# sb6.net
KiCad netlist of a schematic drawn in EAGLE
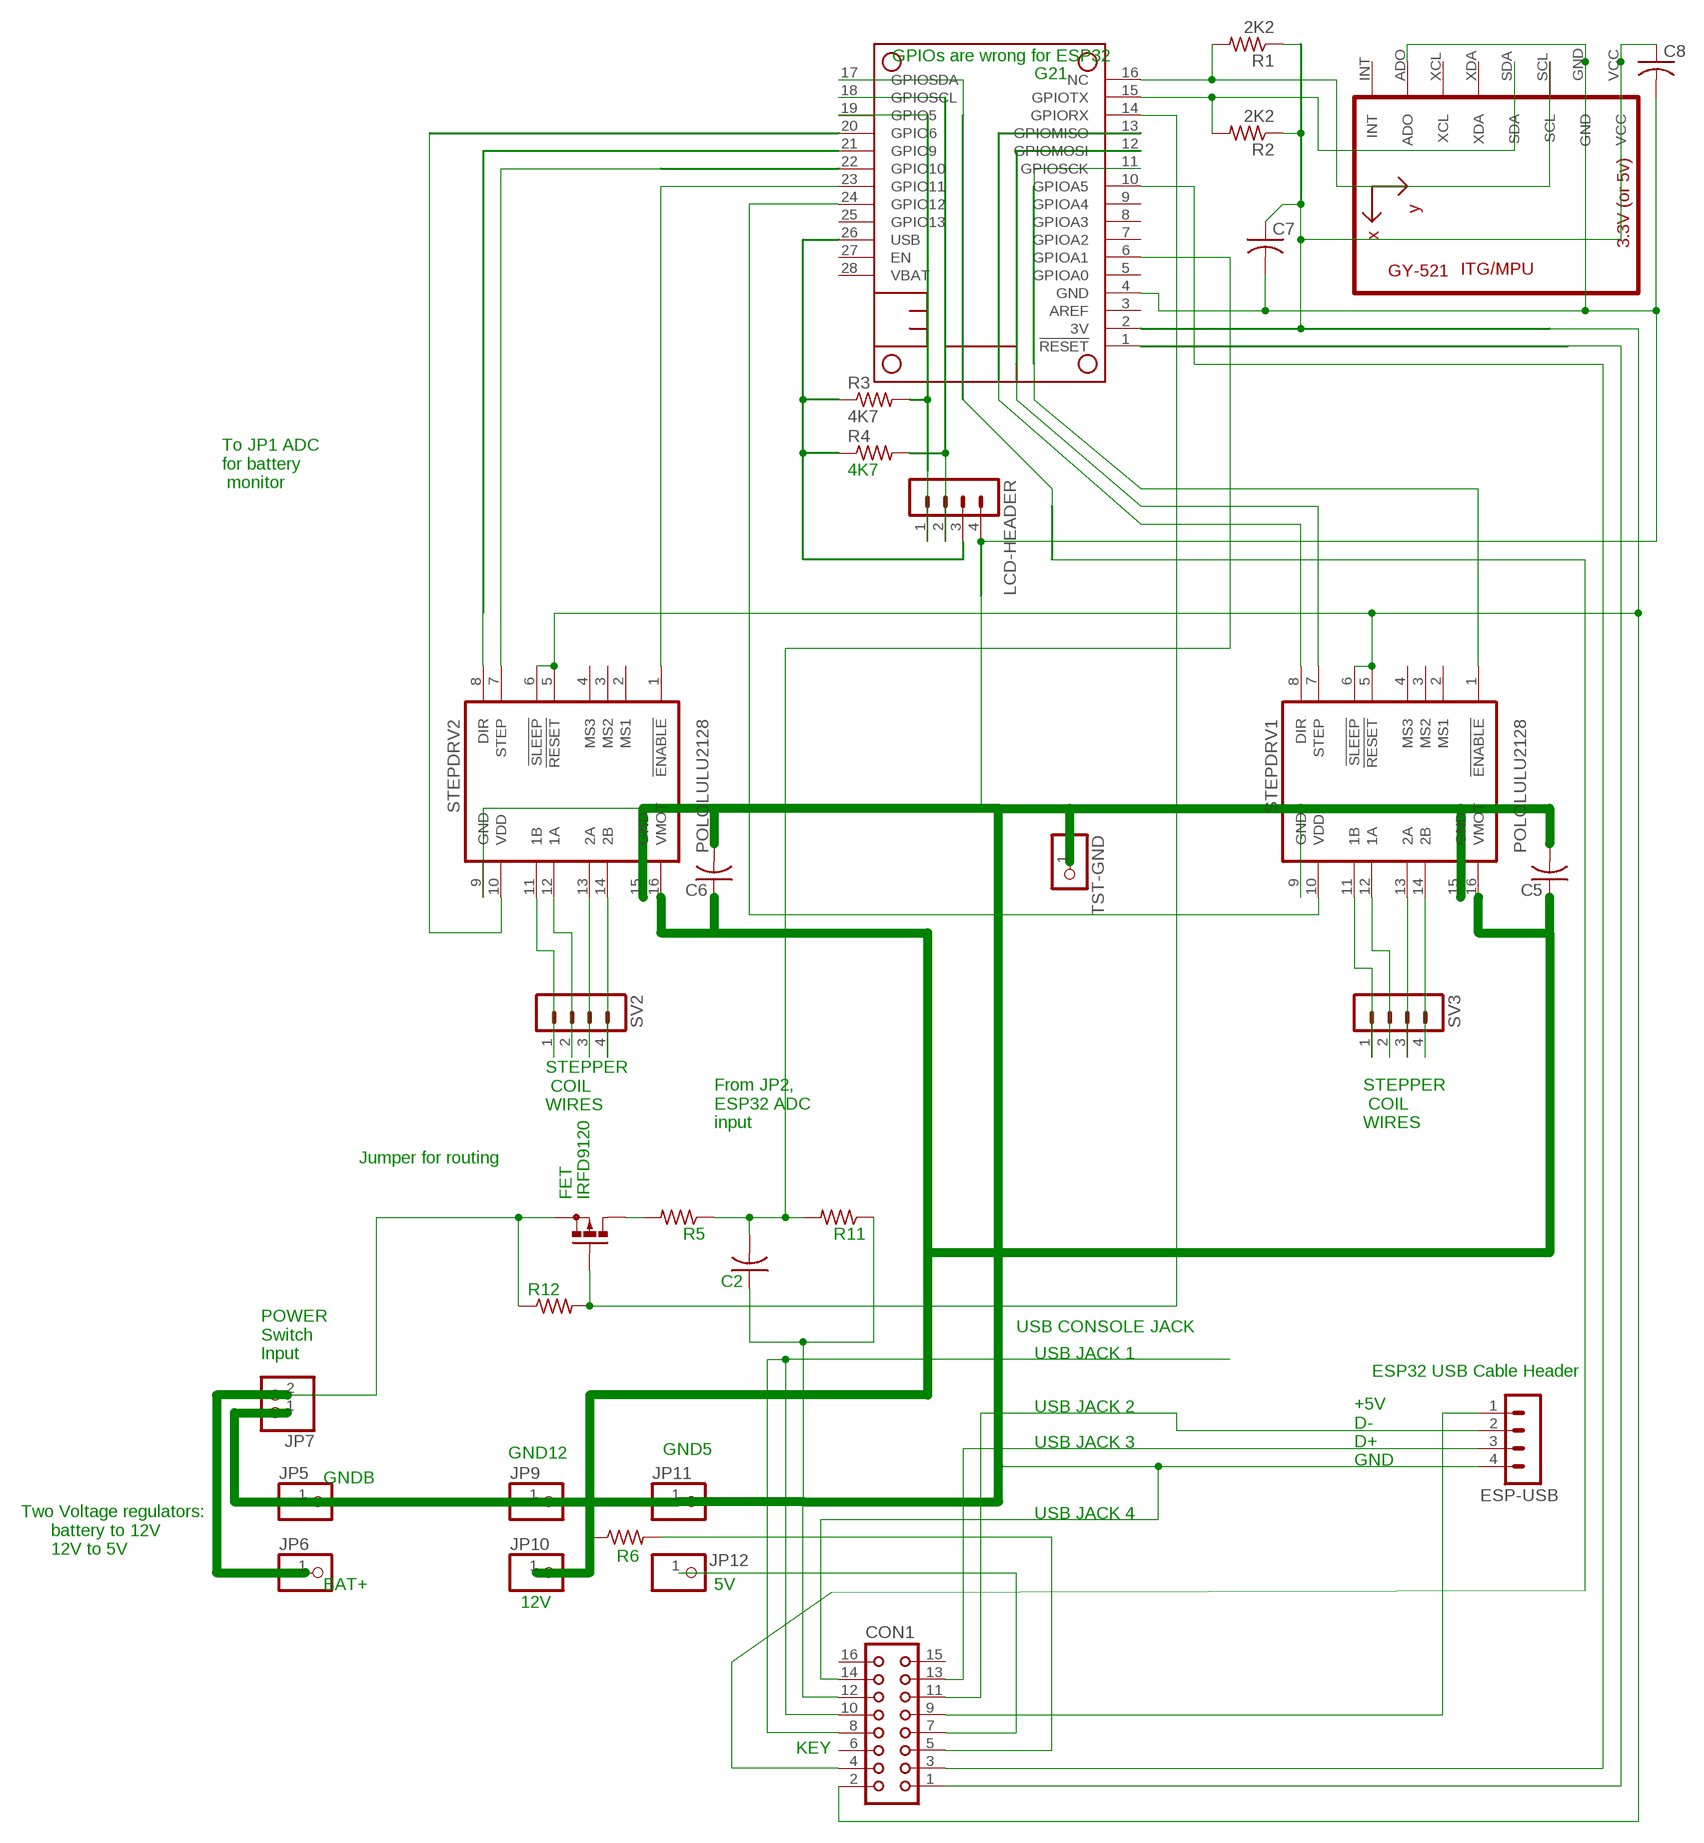
[diagram p0: schematic, sheet 1]

(export (version "E")
  (design (tool "Eeschema 10.0.6"))
  (components
    (comp (ref "C2")
      (value "C-US050-025X075")
      (footprint "eagle-import:C050-025X075")
      (libsource (lib "eagle-import") (part "C-US050-025X075"))
    )
    (comp (ref "C5")
      (value "C-US050-024X044")
      (footprint "eagle-import:C050-024X044")
      (libsource (lib "eagle-import") (part "C-US050-024X044"))
    )
    (comp (ref "C6")
      (value "C-US050-024X044")
      (footprint "eagle-import:C050-024X044")
      (libsource (lib "eagle-import") (part "C-US050-024X044"))
    )
    (comp (ref "C7")
      (value "C-US050-024X044")
      (footprint "eagle-import:C050-024X044")
      (libsource (lib "eagle-import") (part "C-US050-024X044"))
    )
    (comp (ref "C8")
      (value "C-US050-024X044")
      (footprint "eagle-import:C050-024X044")
      (libsource (lib "eagle-import") (part "C-US050-024X044"))
    )
    (comp (ref "CON1")
      (value "CON16")
      (footprint "eagle-import:CON16")
      (libsource (lib "eagle-import") (part "CON16"))
    )
    (comp (ref "ESP-USB")
      (value "MA04-1")
      (footprint "eagle-import:MA04-1")
      (libsource (lib "eagle-import") (part "MA04-1"))
    )
    (comp (ref "FET")
      (value "IRFD9120")
      (footprint "eagle-import:C370-01")
      (libsource (lib "eagle-import") (part "IRFD9120"))
    )
    (comp (ref "JP5")
      (value "PINHD-1X1")
      (footprint "eagle-import:1X01")
      (libsource (lib "eagle-import") (part "PINHD-1X1"))
    )
    (comp (ref "JP6")
      (value "PINHD-1X1")
      (footprint "eagle-import:1X01")
      (libsource (lib "eagle-import") (part "PINHD-1X1"))
    )
    (comp (ref "JP7")
      (value "PINHD-1X2")
      (footprint "eagle-import:1X02")
      (libsource (lib "eagle-import") (part "PINHD-1X2"))
    )
    (comp (ref "JP9")
      (value "PINHD-1X1")
      (footprint "eagle-import:1X01")
      (libsource (lib "eagle-import") (part "PINHD-1X1"))
    )
    (comp (ref "JP10")
      (value "PINHD-1X1")
      (footprint "eagle-import:1X01")
      (libsource (lib "eagle-import") (part "PINHD-1X1"))
    )
    (comp (ref "JP11")
      (value "PINHD-1X1")
      (footprint "eagle-import:1X01")
      (libsource (lib "eagle-import") (part "PINHD-1X1"))
    )
    (comp (ref "JP12")
      (value "PINHD-1X1")
      (footprint "eagle-import:1X01")
      (libsource (lib "eagle-import") (part "PINHD-1X1"))
    )
    (comp (ref "LCD-HEADER")
      (value "MA04-1")
      (footprint "eagle-import:MA04-1")
      (libsource (lib "eagle-import") (part "MA04-1"))
    )
    (comp (ref "MS2")
      (value "FEATHERWING_NOHOLES")
      (footprint "eagle-import:FEATHERWING_NOHOLES")
      (libsource (lib "eagle-import") (part "FEATHERWING_NOHOLES"))
    )
    (comp (ref "R1")
      (value "2K2")
      (footprint "eagle-import:0309_12")
      (libsource (lib "eagle-import") (part "resistor_348_R-US_0309/12"))
    )
    (comp (ref "R2")
      (value "2K2")
      (footprint "eagle-import:0309_12")
      (libsource (lib "eagle-import") (part "resistor_348_R-US_0309/12"))
    )
    (comp (ref "R3")
      (value "4K7")
      (footprint "eagle-import:0309_12")
      (libsource (lib "eagle-import") (part "resistor_348_R-US_0309/12"))
    )
    (comp (ref "R4")
      (value "4K7")
      (footprint "eagle-import:0309_12")
      (libsource (lib "eagle-import") (part "resistor_348_R-US_0309/12"))
    )
    (comp (ref "R5")
      (value "R-US_0207/10")
      (footprint "eagle-import:0207_10")
      (libsource (lib "eagle-import") (part "R-US_0207/10"))
    )
    (comp (ref "R6")
      (value "R-US_0207/10")
      (footprint "eagle-import:0207_10")
      (libsource (lib "eagle-import") (part "R-US_0207/10"))
    )
    (comp (ref "R11")
      (value "R-US_0207/10")
      (footprint "eagle-import:0207_10")
      (libsource (lib "eagle-import") (part "R-US_0207/10"))
    )
    (comp (ref "R12")
      (value "R-US_0207/10")
      (footprint "eagle-import:0207_10")
      (libsource (lib "eagle-import") (part "R-US_0207/10"))
    )
    (comp (ref "STEPDRV1")
      (value "POLOLULU2128")
      (footprint "eagle-import:POLOLULU2128")
      (libsource (lib "eagle-import") (part "POLOLULU2128"))
    )
    (comp (ref "STEPDRV2")
      (value "POLOLULU2128")
      (footprint "eagle-import:POLOLULU2128")
      (libsource (lib "eagle-import") (part "POLOLULU2128"))
    )
    (comp (ref "SV2")
      (value "MA04-1")
      (footprint "eagle-import:MA04-1")
      (libsource (lib "eagle-import") (part "MA04-1"))
    )
    (comp (ref "SV3")
      (value "MA04-1")
      (footprint "eagle-import:MA04-1")
      (libsource (lib "eagle-import") (part "MA04-1"))
    )
    (comp (ref "TST-GND")
      (value "PINHD-1X1")
      (footprint "eagle-import:1X01")
      (libsource (lib "eagle-import") (part "PINHD-1X1"))
    )
    (comp (ref "U1")
      (value "GY-521MPU6050")
      (footprint "eagle-import:GY-521")
      (libsource (lib "eagle-import") (part "GY-521MPU6050"))
    )
  )
  (nets
    (net (code "1") (name "/VBAT") (class "Default")
      (node (ref "MS2") (pin "28") (pinfunction "VBAT_28") (pintype "power_in"))
    )
    (net (code "2") (name "Net-(CON1-Pad5)") (class "Default")
      (node (ref "CON1") (pin "5") (pinfunction "5_5") (pintype "passive"))
      (node (ref "R6") (pin "2") (pinfunction "2_2") (pintype "passive"))
    )
    (net (code "3") (name "Net-(CON1-Pad7)") (class "Default")
      (node (ref "CON1") (pin "7") (pinfunction "7_7") (pintype "passive"))
      (node (ref "JP12") (pin "1") (pinfunction "1_1") (pintype "passive"))
    )
    (net (code "4") (name "Net-(CON1-Pad9)") (class "Default")
      (node (ref "CON1") (pin "9") (pinfunction "9_9") (pintype "passive"))
      (node (ref "ESP-USB") (pin "1") (pinfunction "1_1") (pintype "passive"))
    )
    (net (code "5") (name "Net-(CON1-Pad10)") (class "Default")
      (node (ref "CON1") (pin "10") (pinfunction "10_10") (pintype "passive"))
      (node (ref "CON1") (pin "8") (pinfunction "8_8") (pintype "passive"))
    )
    (net (code "6") (name "Net-(CON1-Pad11)") (class "Default")
      (node (ref "CON1") (pin "11") (pinfunction "11_11") (pintype "passive"))
      (node (ref "ESP-USB") (pin "2") (pinfunction "2_2") (pintype "passive"))
    )
    (net (code "7") (name "Net-(CON1-Pad13)") (class "Default")
      (node (ref "CON1") (pin "13") (pinfunction "13_13") (pintype "passive"))
      (node (ref "ESP-USB") (pin "3") (pinfunction "3_3") (pintype "passive"))
    )
    (net (code "8") (name "Net-(FET-D-PadD1)") (class "Default")
      (node (ref "FET") (pin "D") (pinfunction "D_D") (pintype "passive"))
      (node (ref "FET") (pin "D1") (pinfunction "D_D1") (pintype "passive"))
      (node (ref "R5") (pin "2") (pinfunction "2_2") (pintype "passive"))
    )
    (net (code "9") (name "Net-(FET-PadS)") (class "Default")
      (node (ref "FET") (pin "S") (pinfunction "S_S") (pintype "passive"))
      (node (ref "JP6") (pin "1") (pinfunction "1_1") (pintype "passive"))
      (node (ref "JP7") (pin "2") (pinfunction "2_2") (pintype "passive"))
      (node (ref "R12") (pin "1") (pinfunction "1_1") (pintype "passive"))
    )
    (net (code "10") (name "Net-(MS2-3V)") (class "Default")
      (node (ref "C7") (pin "1") (pinfunction "1_1") (pintype "passive"))
      (node (ref "C8") (pin "1") (pinfunction "1_1") (pintype "passive"))
      (node (ref "CON1") (pin "2") (pinfunction "2_2") (pintype "passive"))
      (node (ref "MS2") (pin "2") (pinfunction "3V_2") (pintype "power_in"))
      (node (ref "R1") (pin "1") (pinfunction "1_1") (pintype "passive"))
      (node (ref "R2") (pin "1") (pinfunction "1_1") (pintype "passive"))
      (node (ref "STEPDRV1") (pin "5") (pinfunction "~{RESET}_5") (pintype "input"))
      (node (ref "STEPDRV1") (pin "6") (pinfunction "~{SLEEP}_6") (pintype "input"))
      (node (ref "STEPDRV2") (pin "5") (pinfunction "~{RESET}_5") (pintype "input"))
      (node (ref "STEPDRV2") (pin "6") (pinfunction "~{SLEEP}_6") (pintype "input"))
      (node (ref "U1") (pin "VCC") (pinfunction "VCC_VCC") (pintype "bidirectional"))
    )
    (net (code "11") (name "Net-(MS2-GND)") (class "Default")
      (node (ref "C2") (pin "1") (pinfunction "1_1") (pintype "passive"))
      (node (ref "C5") (pin "2") (pinfunction "2_2") (pintype "passive"))
      (node (ref "C6") (pin "2") (pinfunction "2_2") (pintype "passive"))
      (node (ref "C7") (pin "2") (pinfunction "2_2") (pintype "passive"))
      (node (ref "C8") (pin "2") (pinfunction "2_2") (pintype "passive"))
      (node (ref "CON1") (pin "12") (pinfunction "12_12") (pintype "passive"))
      (node (ref "CON1") (pin "14") (pinfunction "14_14") (pintype "passive"))
      (node (ref "ESP-USB") (pin "4") (pinfunction "4_4") (pintype "passive"))
      (node (ref "JP11") (pin "1") (pinfunction "1_1") (pintype "passive"))
      (node (ref "JP5") (pin "1") (pinfunction "1_1") (pintype "passive"))
      (node (ref "JP7") (pin "1") (pinfunction "1_1") (pintype "passive"))
      (node (ref "JP9") (pin "1") (pinfunction "1_1") (pintype "passive"))
      (node (ref "LCD-HEADER") (pin "4") (pinfunction "4_4") (pintype "passive"))
      (node (ref "MS2") (pin "4") (pinfunction "GND_4") (pintype "power_in"))
      (node (ref "R11") (pin "1") (pinfunction "1_1") (pintype "passive"))
      (node (ref "STEPDRV1") (pin "15") (pinfunction "GND_15") (pintype "power_in"))
      (node (ref "STEPDRV1") (pin "9") (pinfunction "GND_9") (pintype "power_in"))
      (node (ref "STEPDRV2") (pin "15") (pinfunction "GND_15") (pintype "power_in"))
      (node (ref "STEPDRV2") (pin "9") (pinfunction "GND_9") (pintype "power_in"))
      (node (ref "TST-GND") (pin "1") (pinfunction "1_1") (pintype "passive"))
      (node (ref "U1") (pin "ADO") (pinfunction "ADO_ADO") (pintype "bidirectional"))
      (node (ref "U1") (pin "GND") (pinfunction "GND_GND") (pintype "bidirectional"))
    )
    (net (code "12") (name "Net-(MS2-GPIO5)") (class "Default")
      (node (ref "LCD-HEADER") (pin "1") (pinfunction "1_1") (pintype "passive"))
      (node (ref "MS2") (pin "19") (pinfunction "GPIO5_19") (pintype "bidirectional"))
      (node (ref "R3") (pin "2") (pinfunction "2_2") (pintype "passive"))
    )
    (net (code "13") (name "Net-(MS2-GPIO6)") (class "Default")
      (node (ref "MS2") (pin "20") (pinfunction "GPIO6_20") (pintype "bidirectional"))
      (node (ref "STEPDRV2") (pin "10") (pinfunction "VDD_10") (pintype "power_in"))
    )
    (net (code "14") (name "Net-(MS2-GPIO9)") (class "Default")
      (node (ref "MS2") (pin "21") (pinfunction "GPIO9_21") (pintype "bidirectional"))
      (node (ref "STEPDRV2") (pin "8") (pinfunction "DIR_8") (pintype "input"))
    )
    (net (code "15") (name "Net-(MS2-GPIO10)") (class "Default")
      (node (ref "MS2") (pin "22") (pinfunction "GPIO10_22") (pintype "bidirectional"))
      (node (ref "STEPDRV2") (pin "7") (pinfunction "STEP_7") (pintype "input"))
    )
    (net (code "16") (name "Net-(MS2-GPIO11)") (class "Default")
      (node (ref "MS2") (pin "23") (pinfunction "GPIO11_23") (pintype "bidirectional"))
      (node (ref "STEPDRV2") (pin "1") (pinfunction "~{ENABLE}_1") (pintype "input"))
    )
    (net (code "17") (name "Net-(MS2-GPIO12)") (class "Default")
      (node (ref "MS2") (pin "24") (pinfunction "GPIO12_24") (pintype "bidirectional"))
      (node (ref "STEPDRV1") (pin "10") (pinfunction "VDD_10") (pintype "power_in"))
    )
    (net (code "18") (name "Net-(MS2-GPIOA1)") (class "Default")
      (node (ref "C2") (pin "2") (pinfunction "2_2") (pintype "passive"))
      (node (ref "MS2") (pin "6") (pinfunction "GPIOA1_6") (pintype "bidirectional"))
      (node (ref "R11") (pin "2") (pinfunction "2_2") (pintype "passive"))
      (node (ref "R5") (pin "1") (pinfunction "1_1") (pintype "passive"))
    )
    (net (code "19") (name "Net-(MS2-GPIOA5)") (class "Default")
      (node (ref "CON1") (pin "3") (pinfunction "3_3") (pintype "passive"))
      (node (ref "MS2") (pin "10") (pinfunction "GPIOA5_10") (pintype "bidirectional"))
    )
    (net (code "20") (name "Net-(MS2-GPIOMISO)") (class "Default")
      (node (ref "MS2") (pin "13") (pinfunction "GPIOMISO_13") (pintype "bidirectional"))
      (node (ref "STEPDRV1") (pin "8") (pinfunction "DIR_8") (pintype "input"))
    )
    (net (code "21") (name "Net-(MS2-GPIOMOSI)") (class "Default")
      (node (ref "MS2") (pin "12") (pinfunction "GPIOMOSI_12") (pintype "bidirectional"))
      (node (ref "STEPDRV1") (pin "7") (pinfunction "STEP_7") (pintype "input"))
    )
    (net (code "22") (name "Net-(MS2-GPIORX)") (class "Default")
      (node (ref "FET") (pin "G") (pinfunction "G_G") (pintype "passive"))
      (node (ref "MS2") (pin "14") (pinfunction "GPIORX_14") (pintype "bidirectional"))
      (node (ref "R12") (pin "2") (pinfunction "2_2") (pintype "passive"))
    )
    (net (code "23") (name "Net-(MS2-GPIOSCK)") (class "Default")
      (node (ref "MS2") (pin "11") (pinfunction "GPIOSCK_11") (pintype "bidirectional"))
      (node (ref "STEPDRV1") (pin "1") (pinfunction "~{ENABLE}_1") (pintype "input"))
    )
    (net (code "24") (name "Net-(MS2-GPIOSCL)") (class "Default")
      (node (ref "LCD-HEADER") (pin "2") (pinfunction "2_2") (pintype "passive"))
      (node (ref "MS2") (pin "18") (pinfunction "GPIOSCL_18") (pintype "bidirectional"))
      (node (ref "R4") (pin "2") (pinfunction "2_2") (pintype "passive"))
    )
    (net (code "25") (name "Net-(MS2-GPIOSDA)") (class "Default")
      (node (ref "CON1") (pin "4") (pinfunction "4_4") (pintype "passive"))
      (node (ref "MS2") (pin "17") (pinfunction "GPIOSDA_17") (pintype "bidirectional"))
    )
    (net (code "26") (name "Net-(MS2-GPIOTX)") (class "Default")
      (node (ref "MS2") (pin "15") (pinfunction "GPIOTX_15") (pintype "bidirectional"))
      (node (ref "R2") (pin "2") (pinfunction "2_2") (pintype "passive"))
      (node (ref "U1") (pin "SDA") (pinfunction "SDA_SDA") (pintype "bidirectional"))
    )
    (net (code "27") (name "Net-(MS2-NC)") (class "Default")
      (node (ref "MS2") (pin "16") (pinfunction "NC_16") (pintype "passive"))
      (node (ref "R1") (pin "2") (pinfunction "2_2") (pintype "passive"))
      (node (ref "U1") (pin "SCL") (pinfunction "SCL_SCL") (pintype "bidirectional"))
    )
    (net (code "28") (name "Net-(MS2-USB)") (class "Default")
      (node (ref "LCD-HEADER") (pin "3") (pinfunction "3_3") (pintype "passive"))
      (node (ref "MS2") (pin "26") (pinfunction "USB_26") (pintype "power_in"))
      (node (ref "R3") (pin "1") (pinfunction "1_1") (pintype "passive"))
      (node (ref "R4") (pin "1") (pinfunction "1_1") (pintype "passive"))
    )
    (net (code "29") (name "Net-(MS2-~{RESET})") (class "Default")
      (node (ref "CON1") (pin "1") (pinfunction "1_1") (pintype "passive"))
      (node (ref "MS2") (pin "1") (pinfunction "~{RESET}_1") (pintype "input"))
    )
    (net (code "30") (name "Net-(STEPDRV1-1A)") (class "Default")
      (node (ref "STEPDRV1") (pin "12") (pinfunction "1A_12") (pintype "output"))
      (node (ref "SV3") (pin "2") (pinfunction "2_2") (pintype "passive"))
    )
    (net (code "31") (name "Net-(STEPDRV1-1B)") (class "Default")
      (node (ref "STEPDRV1") (pin "11") (pinfunction "1B_11") (pintype "output"))
      (node (ref "SV3") (pin "1") (pinfunction "1_1") (pintype "passive"))
    )
    (net (code "32") (name "Net-(STEPDRV1-2A)") (class "Default")
      (node (ref "STEPDRV1") (pin "13") (pinfunction "2A_13") (pintype "output"))
      (node (ref "SV3") (pin "3") (pinfunction "3_3") (pintype "passive"))
    )
    (net (code "33") (name "Net-(STEPDRV1-2B)") (class "Default")
      (node (ref "STEPDRV1") (pin "14") (pinfunction "2B_14") (pintype "output"))
      (node (ref "SV3") (pin "4") (pinfunction "4_4") (pintype "passive"))
    )
    (net (code "34") (name "Net-(STEPDRV1-VMOT)") (class "Default")
      (node (ref "C5") (pin "1") (pinfunction "1_1") (pintype "passive"))
      (node (ref "C6") (pin "1") (pinfunction "1_1") (pintype "passive"))
      (node (ref "JP10") (pin "1") (pinfunction "1_1") (pintype "passive"))
      (node (ref "R6") (pin "1") (pinfunction "1_1") (pintype "passive"))
      (node (ref "STEPDRV1") (pin "16") (pinfunction "VMOT_16") (pintype "power_in"))
      (node (ref "STEPDRV2") (pin "16") (pinfunction "VMOT_16") (pintype "power_in"))
    )
    (net (code "35") (name "Net-(STEPDRV2-1A)") (class "Default")
      (node (ref "STEPDRV2") (pin "12") (pinfunction "1A_12") (pintype "output"))
      (node (ref "SV2") (pin "2") (pinfunction "2_2") (pintype "passive"))
    )
    (net (code "36") (name "Net-(STEPDRV2-1B)") (class "Default")
      (node (ref "STEPDRV2") (pin "11") (pinfunction "1B_11") (pintype "output"))
      (node (ref "SV2") (pin "1") (pinfunction "1_1") (pintype "passive"))
    )
    (net (code "37") (name "Net-(STEPDRV2-2A)") (class "Default")
      (node (ref "STEPDRV2") (pin "13") (pinfunction "2A_13") (pintype "output"))
      (node (ref "SV2") (pin "3") (pinfunction "3_3") (pintype "passive"))
    )
    (net (code "38") (name "Net-(STEPDRV2-2B)") (class "Default")
      (node (ref "STEPDRV2") (pin "14") (pinfunction "2B_14") (pintype "output"))
      (node (ref "SV2") (pin "4") (pinfunction "4_4") (pintype "passive"))
    )
    (net (code "39") (name "unconnected-(CON1-Pad6)") (class "Default")
      (node (ref "CON1") (pin "6") (pinfunction "6_6") (pintype "passive"))
    )
    (net (code "40") (name "unconnected-(CON1-Pad15)") (class "Default")
      (node (ref "CON1") (pin "15") (pinfunction "15_15") (pintype "passive"))
    )
    (net (code "41") (name "unconnected-(CON1-Pad16)") (class "Default")
      (node (ref "CON1") (pin "16") (pinfunction "16_16") (pintype "passive"))
    )
    (net (code "42") (name "unconnected-(MS2-AREF-Pad3)") (class "Default")
      (node (ref "MS2") (pin "3") (pinfunction "AREF_3") (pintype "passive"))
    )
    (net (code "43") (name "unconnected-(MS2-EN-Pad27)") (class "Default")
      (node (ref "MS2") (pin "27") (pinfunction "EN_27") (pintype "passive"))
    )
    (net (code "44") (name "unconnected-(MS2-GPIO13-Pad25)") (class "Default")
      (node (ref "MS2") (pin "25") (pinfunction "GPIO13_25") (pintype "bidirectional"))
    )
    (net (code "45") (name "unconnected-(MS2-GPIOA0-Pad5)") (class "Default")
      (node (ref "MS2") (pin "5") (pinfunction "GPIOA0_5") (pintype "bidirectional"))
    )
    (net (code "46") (name "unconnected-(MS2-GPIOA2-Pad7)") (class "Default")
      (node (ref "MS2") (pin "7") (pinfunction "GPIOA2_7") (pintype "bidirectional"))
    )
    (net (code "47") (name "unconnected-(MS2-GPIOA3-Pad8)") (class "Default")
      (node (ref "MS2") (pin "8") (pinfunction "GPIOA3_8") (pintype "bidirectional"))
    )
    (net (code "48") (name "unconnected-(MS2-GPIOA4-Pad9)") (class "Default")
      (node (ref "MS2") (pin "9") (pinfunction "GPIOA4_9") (pintype "bidirectional"))
    )
    (net (code "49") (name "unconnected-(STEPDRV1-MS1-Pad2)") (class "Default")
      (node (ref "STEPDRV1") (pin "2") (pinfunction "MS1_2") (pintype "input"))
    )
    (net (code "50") (name "unconnected-(STEPDRV1-MS2-Pad3)") (class "Default")
      (node (ref "STEPDRV1") (pin "3") (pinfunction "MS2_3") (pintype "input"))
    )
    (net (code "51") (name "unconnected-(STEPDRV1-MS3-Pad4)") (class "Default")
      (node (ref "STEPDRV1") (pin "4") (pinfunction "MS3_4") (pintype "input"))
    )
    (net (code "52") (name "unconnected-(STEPDRV2-MS1-Pad2)") (class "Default")
      (node (ref "STEPDRV2") (pin "2") (pinfunction "MS1_2") (pintype "input"))
    )
    (net (code "53") (name "unconnected-(STEPDRV2-MS2-Pad3)") (class "Default")
      (node (ref "STEPDRV2") (pin "3") (pinfunction "MS2_3") (pintype "input"))
    )
    (net (code "54") (name "unconnected-(STEPDRV2-MS3-Pad4)") (class "Default")
      (node (ref "STEPDRV2") (pin "4") (pinfunction "MS3_4") (pintype "input"))
    )
    (net (code "55") (name "unconnected-(U1-PadINT)") (class "Default")
      (node (ref "U1") (pin "INT") (pinfunction "INT_INT") (pintype "bidirectional"))
    )
    (net (code "56") (name "unconnected-(U1-PadXCL)") (class "Default")
      (node (ref "U1") (pin "XCL") (pinfunction "XCL_XCL") (pintype "bidirectional"))
    )
    (net (code "57") (name "unconnected-(U1-PadXDA)") (class "Default")
      (node (ref "U1") (pin "XDA") (pinfunction "XDA_XDA") (pintype "bidirectional"))
    )
  )
)
